# PowerSupply.net
KiCad netlist of a schematic drawn in Altium Designer
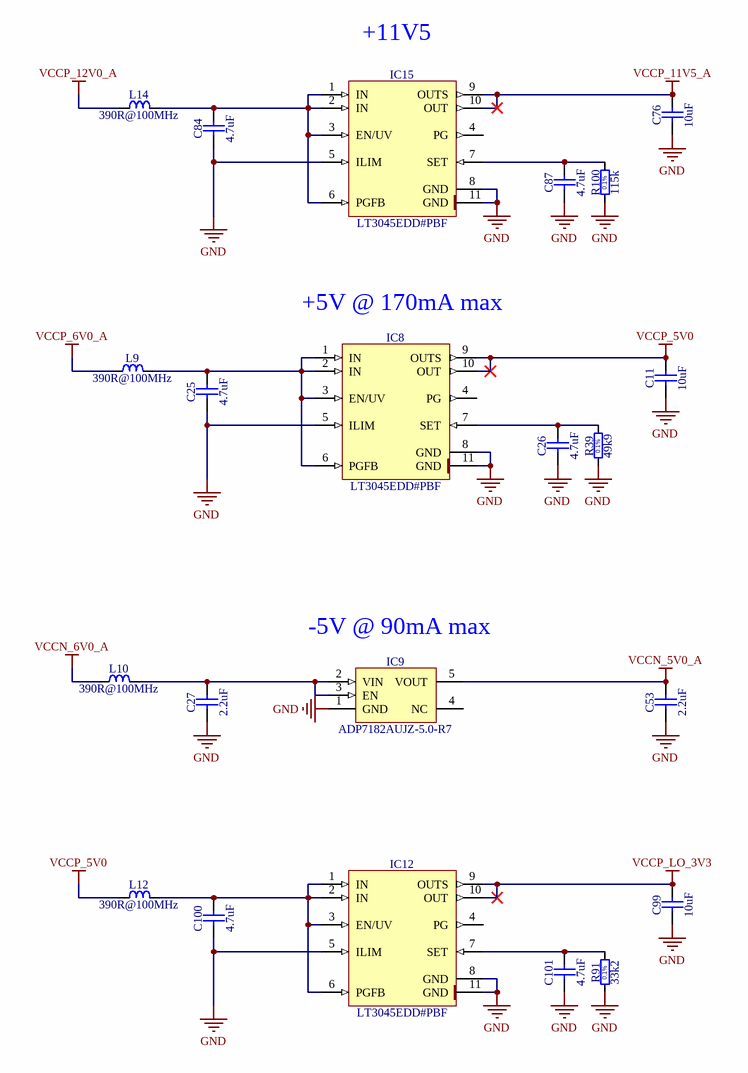
[diagram p0: PowerSupply.SchDoc]

(export (version "E")
  (design (tool "Eeschema 10.0.6"))
  (components
    (comp (ref "C11")
      (value "10uF")
      (footprint "CAPC1608X87N")
      (description "Non-polarised capacitor")
      (fields
        (field (name "PART NUMBER") "CC0603_10UF_6.3V_20%_X5R")
        (field (name "VOLTAGE") "6.3V")
        (field (name "AUTHOR") "CERN DEM JLC")
      )
      (libsource (lib "Capacitors") (part "Capacitor - non polarized"))
    )
    (comp (ref "C25")
      (value "4.7uF")
      (footprint "CAPC1709X95N")
      (description "Non-polarised capacitor")
      (fields
        (field (name "PART NUMBER") "CC0603_4.7UF_16V_10%_X5R")
        (field (name "VOLTAGE") "16V")
        (field (name "AUTHOR") "CERN DEM JLC")
      )
      (libsource (lib "Capacitors") (part "Capacitor - non polarized"))
    )
    (comp (ref "C26")
      (value "4.7uF")
      (footprint "CAPC1709X95N")
      (description "Non-polarised capacitor")
      (fields
        (field (name "PART NUMBER") "CC0603_4.7UF_16V_10%_X5R")
        (field (name "VOLTAGE") "16V")
        (field (name "AUTHOR") "CERN DEM JLC")
      )
      (libsource (lib "Capacitors") (part "Capacitor - non polarized"))
    )
    (comp (ref "C27")
      (value "2.2uF")
      (footprint "CAPC1608X90N")
      (description "Non-polarised capacitor")
      (fields
        (field (name "PART NUMBER") "CC0603_2.2UF_10V_20%_X7R")
        (field (name "VOLTAGE") "10V")
        (field (name "AUTHOR") "CERN DEM JLC")
      )
      (libsource (lib "Capacitors") (part "Capacitor - non polarized"))
    )
    (comp (ref "C53")
      (value "2.2uF")
      (footprint "CAPC1608X90N")
      (description "Non-polarised capacitor")
      (fields
        (field (name "PART NUMBER") "CC0603_2.2UF_10V_20%_X7R")
        (field (name "VOLTAGE") "10V")
        (field (name "AUTHOR") "CERN DEM JLC")
      )
      (libsource (lib "Capacitors") (part "Capacitor - non polarized"))
    )
    (comp (ref "C76")
      (value "10uF")
      (footprint "CAPC1608X87N")
      (description "Non-polarised capacitor")
      (fields
        (field (name "PART NUMBER") "CC0603_10UF_6.3V_20%_X5R")
        (field (name "VOLTAGE") "6.3V")
        (field (name "AUTHOR") "CERN DEM JLC")
      )
      (libsource (lib "Capacitors") (part "Capacitor - non polarized"))
    )
    (comp (ref "C84")
      (value "4.7uF")
      (footprint "CAPC1709X95N")
      (description "Non-polarised capacitor")
      (fields
        (field (name "PART NUMBER") "CC0603_4.7UF_16V_10%_X5R")
        (field (name "VOLTAGE") "16V")
        (field (name "AUTHOR") "CERN DEM JLC")
      )
      (libsource (lib "Capacitors") (part "Capacitor - non polarized"))
    )
    (comp (ref "C87")
      (value "4.7uF")
      (footprint "CAPC1709X95N")
      (description "Non-polarised capacitor")
      (fields
        (field (name "PART NUMBER") "CC0603_4.7UF_16V_10%_X5R")
        (field (name "VOLTAGE") "16V")
        (field (name "AUTHOR") "CERN DEM JLC")
      )
      (libsource (lib "Capacitors") (part "Capacitor - non polarized"))
    )
    (comp (ref "C99")
      (value "10uF")
      (footprint "CAPC1608X87N")
      (description "Non-polarised capacitor")
      (fields
        (field (name "PART NUMBER") "CC0603_10UF_6.3V_20%_X5R")
        (field (name "VOLTAGE") "6.3V")
        (field (name "AUTHOR") "CERN DEM JLC")
      )
      (libsource (lib "Capacitors") (part "Capacitor - non polarized"))
    )
    (comp (ref "C100")
      (value "4.7uF")
      (footprint "CAPC1709X95N")
      (description "Non-polarised capacitor")
      (fields
        (field (name "PART NUMBER") "CC0603_4.7UF_16V_10%_X5R")
        (field (name "VOLTAGE") "16V")
        (field (name "AUTHOR") "CERN DEM JLC")
      )
      (libsource (lib "Capacitors") (part "Capacitor - non polarized"))
    )
    (comp (ref "C101")
      (value "4.7uF")
      (footprint "CAPC1709X95N")
      (description "Non-polarised capacitor")
      (fields
        (field (name "PART NUMBER") "CC0603_4.7UF_16V_10%_X5R")
        (field (name "VOLTAGE") "16V")
        (field (name "AUTHOR") "CERN DEM JLC")
      )
      (libsource (lib "Capacitors") (part "Capacitor - non polarized"))
    )
    (comp (ref "IC8")
      (value "LT3045EDD#PBF")
      (footprint "SON50P300X300X80-11N-R175X248")
      (description "20V, 500mA, Ultralow Noise, Ultrahigh PSRR Linear Regulator")
      (fields (field (name "MANUFACTURER") "LINEAR TECHNOLOGY") (field (name "AUTHOR") "CERN DEM JLC"))
      (libsource (lib "ICs And Semiconductors") (part "LT3045EDD"))
    )
    (comp (ref "IC9")
      (value "ADP7182AUJZ-5.0-R7")
      (footprint "SOT95P280X90-5N")
      (description "–5V, 200 mA, Low Noise, Linear Regulator")
      (fields (field (name "MANUFACTURER") "ANALOG DEVICES") (field (name "AUTHOR") "CERN DEM JLC"))
      (libsource (lib "ICs And Semiconductors") (part "ADP7182AUJZ-X.X-R7"))
    )
    (comp (ref "IC12")
      (value "LT3045EDD#PBF")
      (footprint "SON50P300X300X80-11N-R175X248")
      (description "20V, 500mA, Ultralow Noise, Ultrahigh PSRR Linear Regulator")
      (fields (field (name "MANUFACTURER") "LINEAR TECHNOLOGY") (field (name "AUTHOR") "CERN DEM JLC"))
      (libsource (lib "ICs And Semiconductors") (part "LT3045EDD"))
    )
    (comp (ref "IC15")
      (value "LT3045EDD#PBF")
      (footprint "SON50P300X300X80-11N-R175X248")
      (description "20V, 500mA, Ultralow Noise, Ultrahigh PSRR Linear Regulator")
      (fields (field (name "MANUFACTURER") "LINEAR TECHNOLOGY") (field (name "AUTHOR") "CERN DEM JLC"))
      (libsource (lib "ICs And Semiconductors") (part "LT3045EDD"))
    )
    (comp (ref "L9")
      (value "390R@100MHz")
      (footprint "INDC1608X95N")
      (description "Inductor")
      (fields
        (field (name "PART NUMBER") "IND0603_TDK_MPZ1608R391A")
        (field (name "POWER") "1.2A")
        (field (name "AUTHOR") "CERN DEM JLC")
      )
      (libsource (lib "Inductors & Transformers") (part "Inductor"))
    )
    (comp (ref "L10")
      (value "390R@100MHz")
      (footprint "INDC1608X95N")
      (description "Inductor")
      (fields
        (field (name "PART NUMBER") "IND0603_TDK_MPZ1608R391A")
        (field (name "POWER") "1.2A")
        (field (name "AUTHOR") "CERN DEM JLC")
      )
      (libsource (lib "Inductors & Transformers") (part "Inductor"))
    )
    (comp (ref "L12")
      (value "390R@100MHz")
      (footprint "INDC1608X95N")
      (description "Inductor")
      (fields
        (field (name "PART NUMBER") "IND0603_TDK_MPZ1608R391A")
        (field (name "POWER") "1.2A")
        (field (name "AUTHOR") "CERN DEM JLC")
      )
      (libsource (lib "Inductors & Transformers") (part "Inductor"))
    )
    (comp (ref "L14")
      (value "390R@100MHz")
      (footprint "INDC1608X95N")
      (description "Inductor")
      (fields
        (field (name "PART NUMBER") "IND0603_TDK_MPZ1608R391A")
        (field (name "POWER") "1.2A")
        (field (name "AUTHOR") "CERN DEM JLC")
      )
      (libsource (lib "Inductors & Transformers") (part "Inductor"))
    )
    (comp (ref "R39")
      (value "49k9")
      (footprint "RESC1608X55N")
      (description "Resistor - 0.1%")
      (fields
        (field (name "PART NUMBER") "R0603_49K9_0.1%_0.063W_10PPM")
        (field (name "POWER") "0.063W")
        (field (name "AUTHOR") "CERN DEM JLC")
      )
      (libsource (lib "Resistors") (part "Resistor - 0.1%"))
    )
    (comp (ref "R91")
      (value "33k2")
      (footprint "RESC1608X55N")
      (description "Resistor - 0.1%")
      (fields
        (field (name "PART NUMBER") "R0603_33K2_0.1%_0.063W_10PPM")
        (field (name "POWER") "0.063W")
        (field (name "AUTHOR") "CERN DEM JLC")
      )
      (libsource (lib "Resistors") (part "Resistor - 0.1%"))
    )
    (comp (ref "R100")
      (value "115k")
      (footprint "RESC1608X55N")
      (description "Resistor - 0.1%")
      (fields
        (field (name "PART NUMBER") "R0603_115K_0.1%_0.063W_10PPM")
        (field (name "POWER") "0.063W")
        (field (name "AUTHOR") "CERN DEM JLC")
      )
      (libsource (lib "Resistors") (part "Resistor - 0.1%"))
    )
  )
  (nets
    (net (code "1") (name "GND") (class "Default")
      (node (ref "C100") (pin "1") (pinfunction "1_1") (pintype "passive"))
      (node (ref "C101") (pin "1") (pinfunction "1_1") (pintype "passive"))
      (node (ref "C11") (pin "1") (pinfunction "1_1") (pintype "passive"))
      (node (ref "C25") (pin "1") (pinfunction "1_1") (pintype "passive"))
      (node (ref "C26") (pin "1") (pinfunction "1_1") (pintype "passive"))
      (node (ref "C27") (pin "1") (pinfunction "1_1") (pintype "passive"))
      (node (ref "C53") (pin "1") (pinfunction "1_1") (pintype "passive"))
      (node (ref "C76") (pin "1") (pinfunction "1_1") (pintype "passive"))
      (node (ref "C84") (pin "1") (pinfunction "1_1") (pintype "passive"))
      (node (ref "C87") (pin "1") (pinfunction "1_1") (pintype "passive"))
      (node (ref "C99") (pin "1") (pinfunction "1_1") (pintype "passive"))
      (node (ref "IC12") (pin "11") (pinfunction "GND_11") (pintype "power_in"))
      (node (ref "IC12") (pin "5") (pinfunction "ILIM_5") (pintype "input"))
      (node (ref "IC12") (pin "8") (pinfunction "GND_8") (pintype "power_in"))
      (node (ref "IC15") (pin "11") (pinfunction "GND_11") (pintype "power_in"))
      (node (ref "IC15") (pin "5") (pinfunction "ILIM_5") (pintype "input"))
      (node (ref "IC15") (pin "8") (pinfunction "GND_8") (pintype "power_in"))
      (node (ref "IC8") (pin "11") (pinfunction "GND_11") (pintype "power_in"))
      (node (ref "IC8") (pin "5") (pinfunction "ILIM_5") (pintype "input"))
      (node (ref "IC8") (pin "8") (pinfunction "GND_8") (pintype "power_in"))
      (node (ref "IC9") (pin "1") (pinfunction "GND_1") (pintype "power_in"))
      (node (ref "R100") (pin "1") (pinfunction "1_1") (pintype "passive"))
      (node (ref "R39") (pin "1") (pinfunction "1_1") (pintype "passive"))
      (node (ref "R91") (pin "1") (pinfunction "1_1") (pintype "passive"))
    )
    (net (code "2") (name "Net-(IC8-EN{slash}UV)") (class "Default")
      (node (ref "C25") (pin "2") (pinfunction "2_2") (pintype "passive"))
      (node (ref "IC8") (pin "1") (pinfunction "IN_1") (pintype "input"))
      (node (ref "IC8") (pin "2") (pinfunction "IN_2") (pintype "input"))
      (node (ref "IC8") (pin "3") (pinfunction "EN/UV_3") (pintype "input"))
      (node (ref "IC8") (pin "6") (pinfunction "PGFB_6") (pintype "input"))
      (node (ref "L9") (pin "2") (pinfunction "2_2") (pintype "passive"))
    )
    (net (code "3") (name "Net-(IC8-SET)") (class "Default")
      (node (ref "C26") (pin "2") (pinfunction "2_2") (pintype "passive"))
      (node (ref "IC8") (pin "7") (pinfunction "SET_7") (pintype "input"))
      (node (ref "R39") (pin "2") (pinfunction "2_2") (pintype "passive"))
    )
    (net (code "4") (name "Net-(IC9-EN)") (class "Default")
      (node (ref "C27") (pin "2") (pinfunction "2_2") (pintype "passive"))
      (node (ref "IC9") (pin "2") (pinfunction "VIN_2") (pintype "input"))
      (node (ref "IC9") (pin "3") (pinfunction "EN_3") (pintype "input"))
      (node (ref "L10") (pin "2") (pinfunction "2_2") (pintype "passive"))
    )
    (net (code "5") (name "Net-(IC12-EN{slash}UV)") (class "Default")
      (node (ref "C100") (pin "2") (pinfunction "2_2") (pintype "passive"))
      (node (ref "IC12") (pin "1") (pinfunction "IN_1") (pintype "input"))
      (node (ref "IC12") (pin "2") (pinfunction "IN_2") (pintype "input"))
      (node (ref "IC12") (pin "3") (pinfunction "EN/UV_3") (pintype "input"))
      (node (ref "IC12") (pin "6") (pinfunction "PGFB_6") (pintype "input"))
      (node (ref "L12") (pin "2") (pinfunction "2_2") (pintype "passive"))
    )
    (net (code "6") (name "Net-(IC12-SET)") (class "Default")
      (node (ref "C101") (pin "2") (pinfunction "2_2") (pintype "passive"))
      (node (ref "IC12") (pin "7") (pinfunction "SET_7") (pintype "input"))
      (node (ref "R91") (pin "2") (pinfunction "2_2") (pintype "passive"))
    )
    (net (code "7") (name "Net-(IC15-EN{slash}UV)") (class "Default")
      (node (ref "C84") (pin "2") (pinfunction "2_2") (pintype "passive"))
      (node (ref "IC15") (pin "1") (pinfunction "IN_1") (pintype "input"))
      (node (ref "IC15") (pin "2") (pinfunction "IN_2") (pintype "input"))
      (node (ref "IC15") (pin "3") (pinfunction "EN/UV_3") (pintype "input"))
      (node (ref "IC15") (pin "6") (pinfunction "PGFB_6") (pintype "input"))
      (node (ref "L14") (pin "2") (pinfunction "2_2") (pintype "passive"))
    )
    (net (code "8") (name "Net-(IC15-SET)") (class "Default")
      (node (ref "C87") (pin "2") (pinfunction "2_2") (pintype "passive"))
      (node (ref "IC15") (pin "7") (pinfunction "SET_7") (pintype "input"))
      (node (ref "R100") (pin "2") (pinfunction "2_2") (pintype "passive"))
    )
    (net (code "9") (name "VCCN_5V0_A") (class "Default")
      (node (ref "C53") (pin "2") (pinfunction "2_2") (pintype "passive"))
      (node (ref "IC9") (pin "5") (pinfunction "VOUT_5") (pintype "power_in"))
    )
    (net (code "10") (name "VCCN_6V0_A") (class "Default")
      (node (ref "L10") (pin "1") (pinfunction "1_1") (pintype "passive"))
    )
    (net (code "11") (name "VCCP_5V0") (class "Default")
      (node (ref "C11") (pin "2") (pinfunction "2_2") (pintype "passive"))
      (node (ref "IC8") (pin "10") (pinfunction "OUT_10") (pintype "output"))
      (node (ref "IC8") (pin "9") (pinfunction "OUTS_9") (pintype "output"))
      (node (ref "L12") (pin "1") (pinfunction "1_1") (pintype "passive"))
    )
    (net (code "12") (name "VCCP_6V0_A") (class "Default")
      (node (ref "L9") (pin "1") (pinfunction "1_1") (pintype "passive"))
    )
    (net (code "13") (name "VCCP_11V5_A") (class "Default")
      (node (ref "C76") (pin "2") (pinfunction "2_2") (pintype "passive"))
      (node (ref "IC15") (pin "10") (pinfunction "OUT_10") (pintype "output"))
      (node (ref "IC15") (pin "9") (pinfunction "OUTS_9") (pintype "output"))
    )
    (net (code "14") (name "VCCP_12V0_A") (class "Default")
      (node (ref "L14") (pin "1") (pinfunction "1_1") (pintype "passive"))
    )
    (net (code "15") (name "VCCP_LO_3V3") (class "Default")
      (node (ref "C99") (pin "2") (pinfunction "2_2") (pintype "passive"))
      (node (ref "IC12") (pin "10") (pinfunction "OUT_10") (pintype "output"))
      (node (ref "IC12") (pin "9") (pinfunction "OUTS_9") (pintype "output"))
    )
    (net (code "16") (name "unconnected-(IC8-PG-Pad4)") (class "Default")
      (node (ref "IC8") (pin "4") (pinfunction "PG_4") (pintype "output"))
    )
    (net (code "17") (name "unconnected-(IC9-NC-Pad4)") (class "Default")
      (node (ref "IC9") (pin "4") (pinfunction "NC_4") (pintype "passive"))
    )
    (net (code "18") (name "unconnected-(IC12-PG-Pad4)") (class "Default")
      (node (ref "IC12") (pin "4") (pinfunction "PG_4") (pintype "output"))
    )
    (net (code "19") (name "unconnected-(IC15-PG-Pad4)") (class "Default")
      (node (ref "IC15") (pin "4") (pinfunction "PG_4") (pintype "output"))
    )
  )
)
